# LevelShifters.net
KiCad netlist of a schematic drawn in Altium Designer
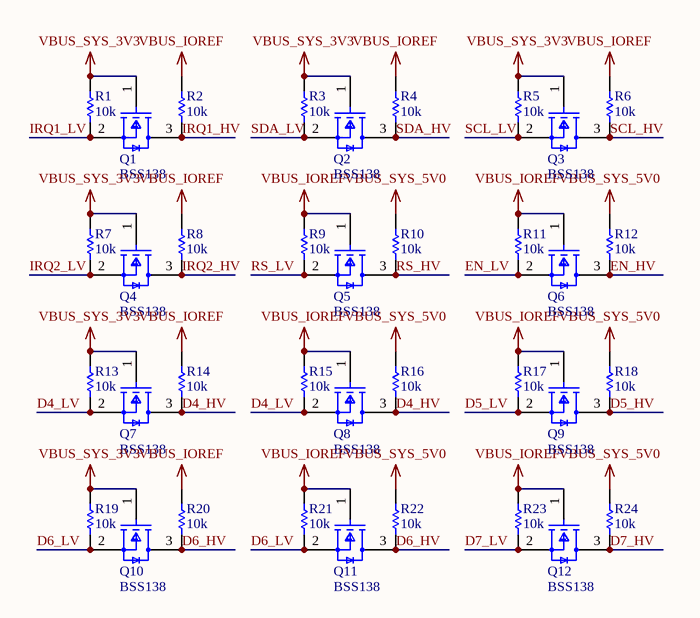
[diagram p0: LevelShifters.SchDoc]

(export (version "E")
  (design (tool "Eeschema 10.0.6"))
  (components
    (comp (ref "Q1")
      (value "BSS138")
      (footprint "FP-318-08-IPC_B")
      (description "MOSFET N-CH 50V 220MA SOT-23")
      (libsource (lib "Altium Content Vault") (part "3b9c635fedb024a5347a57b145af9cc"))
    )
    (comp (ref "Q2")
      (value "BSS138")
      (footprint "FP-318-08-IPC_B")
      (description "MOSFET N-CH 50V 220MA SOT-23")
      (libsource (lib "Altium Content Vault") (part "3b9c635fedb024a5347a57b145af9cc"))
    )
    (comp (ref "Q3")
      (value "BSS138")
      (footprint "FP-318-08-IPC_B")
      (description "MOSFET N-CH 50V 220MA SOT-23")
      (libsource (lib "Altium Content Vault") (part "3b9c635fedb024a5347a57b145af9cc"))
    )
    (comp (ref "Q4")
      (value "BSS138")
      (footprint "FP-318-08-IPC_B")
      (description "MOSFET N-CH 50V 220MA SOT-23")
      (libsource (lib "Altium Content Vault") (part "3b9c635fedb024a5347a57b145af9cc"))
    )
    (comp (ref "Q5")
      (value "BSS138")
      (footprint "FP-318-08-IPC_B")
      (description "MOSFET N-CH 50V 220MA SOT-23")
      (libsource (lib "Altium Content Vault") (part "3b9c635fedb024a5347a57b145af9cc"))
    )
    (comp (ref "Q6")
      (value "BSS138")
      (footprint "FP-318-08-IPC_B")
      (description "MOSFET N-CH 50V 220MA SOT-23")
      (libsource (lib "Altium Content Vault") (part "3b9c635fedb024a5347a57b145af9cc"))
    )
    (comp (ref "Q7")
      (value "BSS138")
      (footprint "FP-318-08-IPC_B")
      (description "MOSFET N-CH 50V 220MA SOT-23")
      (libsource (lib "Altium Content Vault") (part "3b9c635fedb024a5347a57b145af9cc"))
    )
    (comp (ref "Q8")
      (value "BSS138")
      (footprint "FP-318-08-IPC_B")
      (description "MOSFET N-CH 50V 220MA SOT-23")
      (libsource (lib "Altium Content Vault") (part "3b9c635fedb024a5347a57b145af9cc"))
    )
    (comp (ref "Q9")
      (value "BSS138")
      (footprint "FP-318-08-IPC_B")
      (description "MOSFET N-CH 50V 220MA SOT-23")
      (libsource (lib "Altium Content Vault") (part "3b9c635fedb024a5347a57b145af9cc"))
    )
    (comp (ref "Q10")
      (value "BSS138")
      (footprint "FP-318-08-IPC_B")
      (description "MOSFET N-CH 50V 220MA SOT-23")
      (libsource (lib "Altium Content Vault") (part "3b9c635fedb024a5347a57b145af9cc"))
    )
    (comp (ref "Q11")
      (value "BSS138")
      (footprint "FP-318-08-IPC_B")
      (description "MOSFET N-CH 50V 220MA SOT-23")
      (libsource (lib "Altium Content Vault") (part "3b9c635fedb024a5347a57b145af9cc"))
    )
    (comp (ref "Q12")
      (value "BSS138")
      (footprint "FP-318-08-IPC_B")
      (description "MOSFET N-CH 50V 220MA SOT-23")
      (libsource (lib "Altium Content Vault") (part "3b9c635fedb024a5347a57b145af9cc"))
    )
    (comp (ref "R1")
      (value "10k")
      (footprint "0805_RES_HD")
      (description "50k Ohm ±1% 0.125W, 1/8W Surface Mount Resistor Thick Film ±100ppm/°C 0805")
      (fields (field (name "GFUPARTNO") "RC0805FR-07100RL"))
      (libsource (lib "AltiumGFU") (part "ResBasic"))
    )
    (comp (ref "R2")
      (value "10k")
      (footprint "0805_RES_HD")
      (description "50k Ohm ±1% 0.125W, 1/8W Surface Mount Resistor Thick Film ±100ppm/°C 0805")
      (fields (field (name "GFUPARTNO") "RC0805FR-07100RL"))
      (libsource (lib "AltiumGFU") (part "ResBasic"))
    )
    (comp (ref "R3")
      (value "10k")
      (footprint "0805_RES_HD")
      (description "50k Ohm ±1% 0.125W, 1/8W Surface Mount Resistor Thick Film ±100ppm/°C 0805")
      (fields (field (name "GFUPARTNO") "RC0805FR-07100RL"))
      (libsource (lib "AltiumGFU") (part "ResBasic"))
    )
    (comp (ref "R4")
      (value "10k")
      (footprint "0805_RES_HD")
      (description "50k Ohm ±1% 0.125W, 1/8W Surface Mount Resistor Thick Film ±100ppm/°C 0805")
      (fields (field (name "GFUPARTNO") "RC0805FR-07100RL"))
      (libsource (lib "AltiumGFU") (part "ResBasic"))
    )
    (comp (ref "R5")
      (value "10k")
      (footprint "0805_RES_HD")
      (description "50k Ohm ±1% 0.125W, 1/8W Surface Mount Resistor Thick Film ±100ppm/°C 0805")
      (fields (field (name "GFUPARTNO") "RC0805FR-07100RL"))
      (libsource (lib "AltiumGFU") (part "ResBasic"))
    )
    (comp (ref "R6")
      (value "10k")
      (footprint "0805_RES_HD")
      (description "50k Ohm ±1% 0.125W, 1/8W Surface Mount Resistor Thick Film ±100ppm/°C 0805")
      (fields (field (name "GFUPARTNO") "RC0805FR-07100RL"))
      (libsource (lib "AltiumGFU") (part "ResBasic"))
    )
    (comp (ref "R7")
      (value "10k")
      (footprint "0805_RES_HD")
      (description "50k Ohm ±1% 0.125W, 1/8W Surface Mount Resistor Thick Film ±100ppm/°C 0805")
      (fields (field (name "GFUPARTNO") "RC0805FR-07100RL"))
      (libsource (lib "AltiumGFU") (part "ResBasic"))
    )
    (comp (ref "R8")
      (value "10k")
      (footprint "0805_RES_HD")
      (description "50k Ohm ±1% 0.125W, 1/8W Surface Mount Resistor Thick Film ±100ppm/°C 0805")
      (fields (field (name "GFUPARTNO") "RC0805FR-07100RL"))
      (libsource (lib "AltiumGFU") (part "ResBasic"))
    )
    (comp (ref "R9")
      (value "10k")
      (footprint "0805_RES_HD")
      (description "50k Ohm ±1% 0.125W, 1/8W Surface Mount Resistor Thick Film ±100ppm/°C 0805")
      (fields (field (name "GFUPARTNO") "RC0805FR-07100RL"))
      (libsource (lib "AltiumGFU") (part "ResBasic"))
    )
    (comp (ref "R10")
      (value "10k")
      (footprint "0805_RES_HD")
      (description "50k Ohm ±1% 0.125W, 1/8W Surface Mount Resistor Thick Film ±100ppm/°C 0805")
      (fields (field (name "GFUPARTNO") "RC0805FR-07100RL"))
      (libsource (lib "AltiumGFU") (part "ResBasic"))
    )
    (comp (ref "R11")
      (value "10k")
      (footprint "0805_RES_HD")
      (description "50k Ohm ±1% 0.125W, 1/8W Surface Mount Resistor Thick Film ±100ppm/°C 0805")
      (fields (field (name "GFUPARTNO") "RC0805FR-07100RL"))
      (libsource (lib "AltiumGFU") (part "ResBasic"))
    )
    (comp (ref "R12")
      (value "10k")
      (footprint "0805_RES_HD")
      (description "50k Ohm ±1% 0.125W, 1/8W Surface Mount Resistor Thick Film ±100ppm/°C 0805")
      (fields (field (name "GFUPARTNO") "RC0805FR-07100RL"))
      (libsource (lib "AltiumGFU") (part "ResBasic"))
    )
    (comp (ref "R13")
      (value "10k")
      (footprint "0805_RES_HD")
      (description "50k Ohm ±1% 0.125W, 1/8W Surface Mount Resistor Thick Film ±100ppm/°C 0805")
      (fields (field (name "GFUPARTNO") "RC0805FR-07100RL"))
      (libsource (lib "AltiumGFU") (part "ResBasic"))
    )
    (comp (ref "R14")
      (value "10k")
      (footprint "0805_RES_HD")
      (description "50k Ohm ±1% 0.125W, 1/8W Surface Mount Resistor Thick Film ±100ppm/°C 0805")
      (fields (field (name "GFUPARTNO") "RC0805FR-07100RL"))
      (libsource (lib "AltiumGFU") (part "ResBasic"))
    )
    (comp (ref "R15")
      (value "10k")
      (footprint "0805_RES_HD")
      (description "50k Ohm ±1% 0.125W, 1/8W Surface Mount Resistor Thick Film ±100ppm/°C 0805")
      (fields (field (name "GFUPARTNO") "RC0805FR-07100RL"))
      (libsource (lib "AltiumGFU") (part "ResBasic"))
    )
    (comp (ref "R16")
      (value "10k")
      (footprint "0805_RES_HD")
      (description "50k Ohm ±1% 0.125W, 1/8W Surface Mount Resistor Thick Film ±100ppm/°C 0805")
      (fields (field (name "GFUPARTNO") "RC0805FR-07100RL"))
      (libsource (lib "AltiumGFU") (part "ResBasic"))
    )
    (comp (ref "R17")
      (value "10k")
      (footprint "0805_RES_HD")
      (description "50k Ohm ±1% 0.125W, 1/8W Surface Mount Resistor Thick Film ±100ppm/°C 0805")
      (fields (field (name "GFUPARTNO") "RC0805FR-07100RL"))
      (libsource (lib "AltiumGFU") (part "ResBasic"))
    )
    (comp (ref "R18")
      (value "10k")
      (footprint "0805_RES_HD")
      (description "50k Ohm ±1% 0.125W, 1/8W Surface Mount Resistor Thick Film ±100ppm/°C 0805")
      (fields (field (name "GFUPARTNO") "RC0805FR-07100RL"))
      (libsource (lib "AltiumGFU") (part "ResBasic"))
    )
    (comp (ref "R19")
      (value "10k")
      (footprint "0805_RES_HD")
      (description "50k Ohm ±1% 0.125W, 1/8W Surface Mount Resistor Thick Film ±100ppm/°C 0805")
      (fields (field (name "GFUPARTNO") "RC0805FR-07100RL"))
      (libsource (lib "AltiumGFU") (part "ResBasic"))
    )
    (comp (ref "R20")
      (value "10k")
      (footprint "0805_RES_HD")
      (description "50k Ohm ±1% 0.125W, 1/8W Surface Mount Resistor Thick Film ±100ppm/°C 0805")
      (fields (field (name "GFUPARTNO") "RC0805FR-07100RL"))
      (libsource (lib "AltiumGFU") (part "ResBasic"))
    )
    (comp (ref "R21")
      (value "10k")
      (footprint "0805_RES_HD")
      (description "50k Ohm ±1% 0.125W, 1/8W Surface Mount Resistor Thick Film ±100ppm/°C 0805")
      (fields (field (name "GFUPARTNO") "RC0805FR-07100RL"))
      (libsource (lib "AltiumGFU") (part "ResBasic"))
    )
    (comp (ref "R22")
      (value "10k")
      (footprint "0805_RES_HD")
      (description "50k Ohm ±1% 0.125W, 1/8W Surface Mount Resistor Thick Film ±100ppm/°C 0805")
      (fields (field (name "GFUPARTNO") "RC0805FR-07100RL"))
      (libsource (lib "AltiumGFU") (part "ResBasic"))
    )
    (comp (ref "R23")
      (value "10k")
      (footprint "0805_RES_HD")
      (description "50k Ohm ±1% 0.125W, 1/8W Surface Mount Resistor Thick Film ±100ppm/°C 0805")
      (fields (field (name "GFUPARTNO") "RC0805FR-07100RL"))
      (libsource (lib "AltiumGFU") (part "ResBasic"))
    )
    (comp (ref "R24")
      (value "10k")
      (footprint "0805_RES_HD")
      (description "50k Ohm ±1% 0.125W, 1/8W Surface Mount Resistor Thick Film ±100ppm/°C 0805")
      (fields (field (name "GFUPARTNO") "RC0805FR-07100RL"))
      (libsource (lib "AltiumGFU") (part "ResBasic"))
    )
  )
  (nets
    (net (code "1") (name "/D4_HV") (class "Default")
      (node (ref "Q7") (pin "3") (pinfunction "D_3") (pintype "passive"))
      (node (ref "Q8") (pin "3") (pinfunction "D_3") (pintype "passive"))
      (node (ref "R14") (pin "2") (pinfunction "2_2") (pintype "passive"))
      (node (ref "R16") (pin "2") (pinfunction "2_2") (pintype "passive"))
    )
    (net (code "2") (name "/D4_LV") (class "Default")
      (node (ref "Q7") (pin "2") (pinfunction "S_2") (pintype "passive"))
      (node (ref "Q8") (pin "2") (pinfunction "S_2") (pintype "passive"))
      (node (ref "R13") (pin "2") (pinfunction "2_2") (pintype "passive"))
      (node (ref "R15") (pin "2") (pinfunction "2_2") (pintype "passive"))
    )
    (net (code "3") (name "/D5_HV") (class "Default")
      (node (ref "Q9") (pin "3") (pinfunction "D_3") (pintype "passive"))
      (node (ref "R18") (pin "2") (pinfunction "2_2") (pintype "passive"))
    )
    (net (code "4") (name "/D5_LV") (class "Default")
      (node (ref "Q9") (pin "2") (pinfunction "S_2") (pintype "passive"))
      (node (ref "R17") (pin "2") (pinfunction "2_2") (pintype "passive"))
    )
    (net (code "5") (name "/D6_HV") (class "Default")
      (node (ref "Q10") (pin "3") (pinfunction "D_3") (pintype "passive"))
      (node (ref "Q11") (pin "3") (pinfunction "D_3") (pintype "passive"))
      (node (ref "R20") (pin "2") (pinfunction "2_2") (pintype "passive"))
      (node (ref "R22") (pin "2") (pinfunction "2_2") (pintype "passive"))
    )
    (net (code "6") (name "/D6_LV") (class "Default")
      (node (ref "Q10") (pin "2") (pinfunction "S_2") (pintype "passive"))
      (node (ref "Q11") (pin "2") (pinfunction "S_2") (pintype "passive"))
      (node (ref "R19") (pin "2") (pinfunction "2_2") (pintype "passive"))
      (node (ref "R21") (pin "2") (pinfunction "2_2") (pintype "passive"))
    )
    (net (code "7") (name "/D7_HV") (class "Default")
      (node (ref "Q12") (pin "3") (pinfunction "D_3") (pintype "passive"))
      (node (ref "R24") (pin "2") (pinfunction "2_2") (pintype "passive"))
    )
    (net (code "8") (name "/D7_LV") (class "Default")
      (node (ref "Q12") (pin "2") (pinfunction "S_2") (pintype "passive"))
      (node (ref "R23") (pin "2") (pinfunction "2_2") (pintype "passive"))
    )
    (net (code "9") (name "/EN_HV") (class "Default")
      (node (ref "Q6") (pin "3") (pinfunction "D_3") (pintype "passive"))
      (node (ref "R12") (pin "2") (pinfunction "2_2") (pintype "passive"))
    )
    (net (code "10") (name "/EN_LV") (class "Default")
      (node (ref "Q6") (pin "2") (pinfunction "S_2") (pintype "passive"))
      (node (ref "R11") (pin "2") (pinfunction "2_2") (pintype "passive"))
    )
    (net (code "11") (name "/IRQ1_HV") (class "Default")
      (node (ref "Q1") (pin "3") (pinfunction "D_3") (pintype "passive"))
      (node (ref "R2") (pin "2") (pinfunction "2_2") (pintype "passive"))
    )
    (net (code "12") (name "/IRQ1_LV") (class "Default")
      (node (ref "Q1") (pin "2") (pinfunction "S_2") (pintype "passive"))
      (node (ref "R1") (pin "2") (pinfunction "2_2") (pintype "passive"))
    )
    (net (code "13") (name "/IRQ2_HV") (class "Default")
      (node (ref "Q4") (pin "3") (pinfunction "D_3") (pintype "passive"))
      (node (ref "R8") (pin "2") (pinfunction "2_2") (pintype "passive"))
    )
    (net (code "14") (name "/IRQ2_LV") (class "Default")
      (node (ref "Q4") (pin "2") (pinfunction "S_2") (pintype "passive"))
      (node (ref "R7") (pin "2") (pinfunction "2_2") (pintype "passive"))
    )
    (net (code "15") (name "/RS_HV") (class "Default")
      (node (ref "Q5") (pin "3") (pinfunction "D_3") (pintype "passive"))
      (node (ref "R10") (pin "2") (pinfunction "2_2") (pintype "passive"))
    )
    (net (code "16") (name "/RS_LV") (class "Default")
      (node (ref "Q5") (pin "2") (pinfunction "S_2") (pintype "passive"))
      (node (ref "R9") (pin "2") (pinfunction "2_2") (pintype "passive"))
    )
    (net (code "17") (name "/SCL_HV") (class "Default")
      (node (ref "Q3") (pin "3") (pinfunction "D_3") (pintype "passive"))
      (node (ref "R6") (pin "2") (pinfunction "2_2") (pintype "passive"))
    )
    (net (code "18") (name "/SCL_LV") (class "Default")
      (node (ref "Q3") (pin "2") (pinfunction "S_2") (pintype "passive"))
      (node (ref "R5") (pin "2") (pinfunction "2_2") (pintype "passive"))
    )
    (net (code "19") (name "/SDA_HV") (class "Default")
      (node (ref "Q2") (pin "3") (pinfunction "D_3") (pintype "passive"))
      (node (ref "R4") (pin "2") (pinfunction "2_2") (pintype "passive"))
    )
    (net (code "20") (name "/SDA_LV") (class "Default")
      (node (ref "Q2") (pin "2") (pinfunction "S_2") (pintype "passive"))
      (node (ref "R3") (pin "2") (pinfunction "2_2") (pintype "passive"))
    )
    (net (code "21") (name "VBUS_IOREF") (class "Default")
      (node (ref "Q11") (pin "1") (pinfunction "G_1") (pintype "passive"))
      (node (ref "Q12") (pin "1") (pinfunction "G_1") (pintype "passive"))
      (node (ref "Q5") (pin "1") (pinfunction "G_1") (pintype "passive"))
      (node (ref "Q6") (pin "1") (pinfunction "G_1") (pintype "passive"))
      (node (ref "Q8") (pin "1") (pinfunction "G_1") (pintype "passive"))
      (node (ref "Q9") (pin "1") (pinfunction "G_1") (pintype "passive"))
      (node (ref "R11") (pin "1") (pinfunction "1_1") (pintype "passive"))
      (node (ref "R14") (pin "1") (pinfunction "1_1") (pintype "passive"))
      (node (ref "R15") (pin "1") (pinfunction "1_1") (pintype "passive"))
      (node (ref "R17") (pin "1") (pinfunction "1_1") (pintype "passive"))
      (node (ref "R2") (pin "1") (pinfunction "1_1") (pintype "passive"))
      (node (ref "R20") (pin "1") (pinfunction "1_1") (pintype "passive"))
      (node (ref "R21") (pin "1") (pinfunction "1_1") (pintype "passive"))
      (node (ref "R23") (pin "1") (pinfunction "1_1") (pintype "passive"))
      (node (ref "R4") (pin "1") (pinfunction "1_1") (pintype "passive"))
      (node (ref "R6") (pin "1") (pinfunction "1_1") (pintype "passive"))
      (node (ref "R8") (pin "1") (pinfunction "1_1") (pintype "passive"))
      (node (ref "R9") (pin "1") (pinfunction "1_1") (pintype "passive"))
    )
    (net (code "22") (name "VBUS_SYS_3V3") (class "Default")
      (node (ref "Q1") (pin "1") (pinfunction "G_1") (pintype "passive"))
      (node (ref "Q10") (pin "1") (pinfunction "G_1") (pintype "passive"))
      (node (ref "Q2") (pin "1") (pinfunction "G_1") (pintype "passive"))
      (node (ref "Q3") (pin "1") (pinfunction "G_1") (pintype "passive"))
      (node (ref "Q4") (pin "1") (pinfunction "G_1") (pintype "passive"))
      (node (ref "Q7") (pin "1") (pinfunction "G_1") (pintype "passive"))
      (node (ref "R1") (pin "1") (pinfunction "1_1") (pintype "passive"))
      (node (ref "R13") (pin "1") (pinfunction "1_1") (pintype "passive"))
      (node (ref "R19") (pin "1") (pinfunction "1_1") (pintype "passive"))
      (node (ref "R3") (pin "1") (pinfunction "1_1") (pintype "passive"))
      (node (ref "R5") (pin "1") (pinfunction "1_1") (pintype "passive"))
      (node (ref "R7") (pin "1") (pinfunction "1_1") (pintype "passive"))
    )
    (net (code "23") (name "VBUS_SYS_5V0") (class "Default")
      (node (ref "R10") (pin "1") (pinfunction "1_1") (pintype "passive"))
      (node (ref "R12") (pin "1") (pinfunction "1_1") (pintype "passive"))
      (node (ref "R16") (pin "1") (pinfunction "1_1") (pintype "passive"))
      (node (ref "R18") (pin "1") (pinfunction "1_1") (pintype "passive"))
      (node (ref "R22") (pin "1") (pinfunction "1_1") (pintype "passive"))
      (node (ref "R24") (pin "1") (pinfunction "1_1") (pintype "passive"))
    )
  )
)
